# Project2.net
KiCad netlist of a schematic drawn in EAGLE
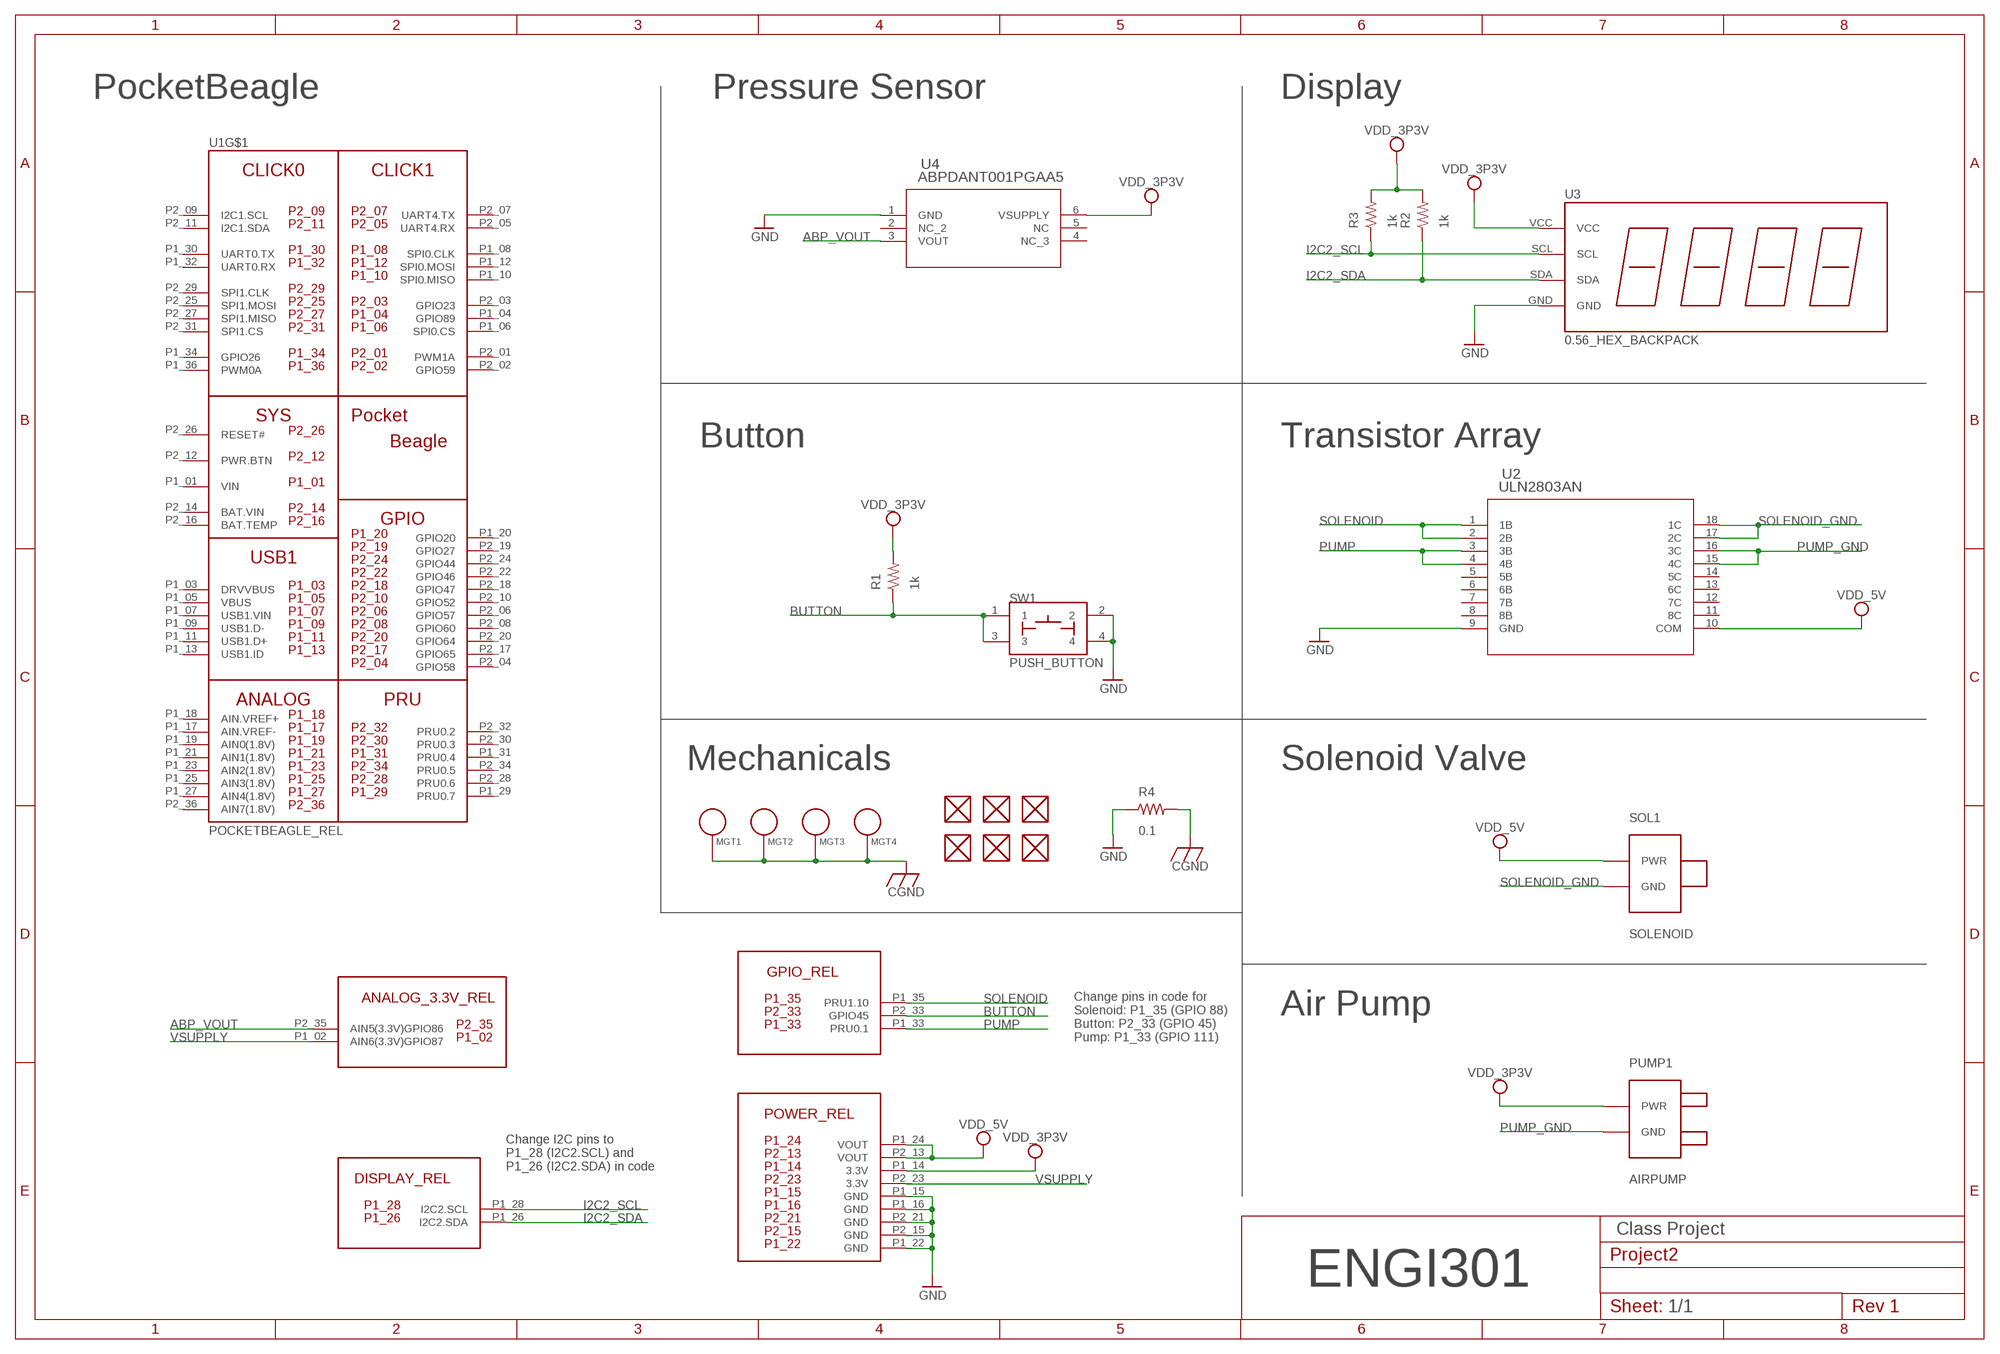
[diagram p0: schematic, sheet 1]

(export (version "E")
  (design (tool "Eeschema 10.0.6"))
  (components
    (comp (ref "FUD1")
      (value "FIDUCIAL")
      (footprint "eagle-import:FIDUCIAL_40MIL")
      (libsource (lib "eagle-import") (part "FIDUCIAL"))
    )
    (comp (ref "FUD2")
      (value "FIDUCIAL")
      (footprint "eagle-import:FIDUCIAL_40MIL")
      (libsource (lib "eagle-import") (part "FIDUCIAL"))
    )
    (comp (ref "FUD3")
      (value "FIDUCIAL")
      (footprint "eagle-import:FIDUCIAL_40MIL")
      (libsource (lib "eagle-import") (part "FIDUCIAL"))
    )
    (comp (ref "FUD4")
      (value "FIDUCIAL")
      (footprint "eagle-import:FIDUCIAL_40MIL")
      (libsource (lib "eagle-import") (part "FIDUCIAL"))
    )
    (comp (ref "FUD5")
      (value "FIDUCIAL")
      (footprint "eagle-import:FIDUCIAL_40MIL")
      (libsource (lib "eagle-import") (part "FIDUCIAL"))
    )
    (comp (ref "FUD6")
      (value "FIDUCIAL")
      (footprint "eagle-import:FIDUCIAL_40MIL")
      (libsource (lib "eagle-import") (part "FIDUCIAL"))
    )
    (comp (ref "MGT1")
      (value "MOUNTING_HOLE")
      (footprint "eagle-import:MOUNTING_HOLE")
      (libsource (lib "eagle-import") (part "MOUNTING_HOLE"))
    )
    (comp (ref "MGT2")
      (value "MOUNTING_HOLE")
      (footprint "eagle-import:MOUNTING_HOLE")
      (libsource (lib "eagle-import") (part "MOUNTING_HOLE"))
    )
    (comp (ref "MGT3")
      (value "MOUNTING_HOLE")
      (footprint "eagle-import:MOUNTING_HOLE")
      (libsource (lib "eagle-import") (part "MOUNTING_HOLE"))
    )
    (comp (ref "MGT4")
      (value "MOUNTING_HOLE")
      (footprint "eagle-import:MOUNTING_HOLE")
      (libsource (lib "eagle-import") (part "MOUNTING_HOLE"))
    )
    (comp (ref "PUMP1")
      (value "AIRPUMP")
      (footprint "eagle-import:AIRPUMP")
      (libsource (lib "eagle-import") (part "AIRPUMP"))
    )
    (comp (ref "R1")
      (value "1k")
      (footprint "eagle-import:R0603")
      (libsource (lib "eagle-import") (part "R_R0603"))
    )
    (comp (ref "R2")
      (value "1k")
      (footprint "eagle-import:R0603")
      (libsource (lib "eagle-import") (part "R_R0603"))
    )
    (comp (ref "R3")
      (value "1k")
      (footprint "eagle-import:R0603")
      (libsource (lib "eagle-import") (part "R_R0603"))
    )
    (comp (ref "R4")
      (value "0.1")
      (footprint "eagle-import:R0603")
      (libsource (lib "eagle-import") (part "R_R0603"))
    )
    (comp (ref "SOL1")
      (value "SOLENOID")
      (footprint "eagle-import:SOLENOID")
      (libsource (lib "eagle-import") (part "SOLENOID"))
    )
    (comp (ref "SW1")
      (value "PUSH_BUTTON")
      (footprint "eagle-import:BUTTON_12.5MM")
      (libsource (lib "eagle-import") (part "PUSH_BUTTON"))
    )
    (comp (ref "U1")
      (value "POCKETBEAGLE_REL")
      (footprint "eagle-import:POCKETBEAGLE")
      (libsource (lib "eagle-import") (part "POCKETBEAGLE_REL"))
    )
    (comp (ref "U2")
      (value "ULN2803AN")
      (footprint "eagle-import:N18_TEX")
      (fields (field (name "COPYRIGHT") "Copyright (C) 2021 Ultra Librarian. All rights reserved."))
      (libsource (lib "eagle-import") (part "ULN2803AN"))
    )
    (comp (ref "U3")
      (value "0.56_HEX_BACKPACK")
      (footprint "eagle-import:0.56_HEX_BACKPACK")
      (libsource (lib "eagle-import") (part "0.56_HEX_BACKPACK"))
    )
    (comp (ref "U4")
      (value "ABPDANT001PGAA5")
      (footprint "eagle-import:ABPDAN_HNW")
      (fields
        (field (name "MANUFACTURER_PART_NUMBER") "ABPDANT005PGAA5")
        (field (name "COPYRIGHT") "Copyright (C) 2021 Ultra Librarian. All rights reserved.")
      )
      (libsource (lib "eagle-import") (part "ABPDANT001PGAA5"))
    )
  )
  (nets
    (net (code "1") (name "/ABP_VOUT") (class "Default")
      (node (ref "U1") (pin "P2_35") (pinfunction "AIN5(3.3V)GPIO86_P2_35") (pintype "bidirectional"))
      (node (ref "U4") (pin "3") (pinfunction "VOUT_3") (pintype "output"))
    )
    (net (code "2") (name "/BAT.VIN") (class "Default")
      (node (ref "U1") (pin "P2_14") (pinfunction "BAT.VIN_P2_14") (pintype "power_in"))
    )
    (net (code "3") (name "/BUTTON") (class "Default")
      (node (ref "R1") (pin "1") (pinfunction "1_1") (pintype "passive"))
      (node (ref "SW1") (pin "1") (pinfunction "1_1") (pintype "bidirectional"))
      (node (ref "SW1") (pin "3") (pinfunction "3_3") (pintype "bidirectional"))
      (node (ref "U1") (pin "P2_33") (pinfunction "GPIO45_P2_33") (pintype "bidirectional"))
    )
    (net (code "4") (name "/I2C2_SCL") (class "Default")
      (node (ref "R3") (pin "1") (pinfunction "1_1") (pintype "passive"))
      (node (ref "U1") (pin "P1_28") (pinfunction "I2C2.SCL_P1_28") (pintype "bidirectional"))
      (node (ref "U3") (pin "SCL") (pinfunction "SCL_SCL") (pintype "bidirectional"))
    )
    (net (code "5") (name "/I2C2_SDA") (class "Default")
      (node (ref "R2") (pin "1") (pinfunction "1_1") (pintype "passive"))
      (node (ref "U1") (pin "P1_26") (pinfunction "I2C2.SDA_P1_26") (pintype "bidirectional"))
      (node (ref "U3") (pin "SDA") (pinfunction "SDA_SDA") (pintype "bidirectional"))
    )
    (net (code "6") (name "/PUMP") (class "Default")
      (node (ref "U1") (pin "P1_33") (pinfunction "PRU0.1_P1_33") (pintype "bidirectional"))
      (node (ref "U2") (pin "3") (pinfunction "3B_3") (pintype "passive"))
      (node (ref "U2") (pin "4") (pinfunction "4B_4") (pintype "passive"))
    )
    (net (code "7") (name "/PUMP_GND") (class "Default")
      (node (ref "PUMP1") (pin "GND1") (pinfunction "GND_GND1") (pintype "bidirectional"))
      (node (ref "U2") (pin "15") (pinfunction "4C_15") (pintype "passive"))
      (node (ref "U2") (pin "16") (pinfunction "3C_16") (pintype "passive"))
    )
    (net (code "8") (name "/SOLENOID") (class "Default")
      (node (ref "U1") (pin "P1_35") (pinfunction "PRU1.10_P1_35") (pintype "bidirectional"))
      (node (ref "U2") (pin "1") (pinfunction "1B_1") (pintype "passive"))
      (node (ref "U2") (pin "2") (pinfunction "2B_2") (pintype "passive"))
    )
    (net (code "9") (name "/SOLENOID_GND") (class "Default")
      (node (ref "SOL1") (pin "GND") (pinfunction "GND_GND") (pintype "bidirectional"))
      (node (ref "U2") (pin "17") (pinfunction "2C_17") (pintype "passive"))
      (node (ref "U2") (pin "18") (pinfunction "1C_18") (pintype "passive"))
    )
    (net (code "10") (name "/VIN") (class "Default")
      (node (ref "U1") (pin "P1_01") (pinfunction "VIN_P1_01") (pintype "power_in"))
    )
    (net (code "11") (name "/VSUPPLY") (class "Default")
      (node (ref "U1") (pin "P1_02") (pinfunction "AIN6(3.3V)GPIO87_P1_02") (pintype "bidirectional"))
      (node (ref "U1") (pin "P2_23") (pinfunction "3.3V_P2_23") (pintype "power_in"))
    )
    (net (code "12") (name "CGND") (class "Default")
      (node (ref "MGT1") (pin "P$1") (pinfunction "P$1_P$1") (pintype "bidirectional"))
      (node (ref "MGT2") (pin "P$1") (pinfunction "P$1_P$1") (pintype "bidirectional"))
      (node (ref "MGT3") (pin "P$1") (pinfunction "P$1_P$1") (pintype "bidirectional"))
      (node (ref "MGT4") (pin "P$1") (pinfunction "P$1_P$1") (pintype "bidirectional"))
      (node (ref "R4") (pin "2") (pinfunction "2_2") (pintype "passive"))
    )
    (net (code "13") (name "GND") (class "Default")
      (node (ref "R4") (pin "1") (pinfunction "1_1") (pintype "passive"))
      (node (ref "SW1") (pin "2") (pinfunction "2_2") (pintype "bidirectional"))
      (node (ref "SW1") (pin "4") (pinfunction "4_4") (pintype "bidirectional"))
      (node (ref "U1") (pin "P1_15") (pinfunction "GND_P1_15") (pintype "power_in"))
      (node (ref "U1") (pin "P1_16") (pinfunction "GND_P1_16") (pintype "power_in"))
      (node (ref "U1") (pin "P1_22") (pinfunction "GND_P1_22") (pintype "power_in"))
      (node (ref "U1") (pin "P2_15") (pinfunction "GND_P2_15") (pintype "power_in"))
      (node (ref "U1") (pin "P2_21") (pinfunction "GND_P2_21") (pintype "power_in"))
      (node (ref "U2") (pin "9") (pinfunction "GND_9") (pintype "passive"))
      (node (ref "U3") (pin "GND") (pinfunction "GND_GND") (pintype "bidirectional"))
      (node (ref "U4") (pin "1") (pinfunction "GND_1") (pintype "passive"))
    )
    (net (code "14") (name "VDD_3P3V") (class "Default")
      (node (ref "PUMP1") (pin "PWR1") (pinfunction "PWR_PWR1") (pintype "bidirectional"))
      (node (ref "R1") (pin "2") (pinfunction "2_2") (pintype "passive"))
      (node (ref "R2") (pin "2") (pinfunction "2_2") (pintype "passive"))
      (node (ref "R3") (pin "2") (pinfunction "2_2") (pintype "passive"))
      (node (ref "U1") (pin "P1_14") (pinfunction "3.3V_P1_14") (pintype "power_in"))
      (node (ref "U3") (pin "VCC") (pinfunction "VCC_VCC") (pintype "power_in"))
      (node (ref "U4") (pin "6") (pinfunction "VSUPPLY_6") (pintype "power_in"))
    )
    (net (code "15") (name "VDD_5V") (class "Default")
      (node (ref "SOL1") (pin "PWR1") (pinfunction "PWR_PWR1") (pintype "bidirectional"))
      (node (ref "U1") (pin "P1_24") (pinfunction "VOUT_P1_24") (pintype "power_in"))
      (node (ref "U1") (pin "P2_13") (pinfunction "VOUT_P2_13") (pintype "power_in"))
      (node (ref "U2") (pin "10") (pinfunction "COM_10") (pintype "passive"))
    )
    (net (code "16") (name "unconnected-(FUD1-PadP$1)") (class "Default")
      (node (ref "FUD1") (pin "P$1") (pinfunction "P$1_P$1") (pintype "no_connect"))
    )
    (net (code "17") (name "unconnected-(FUD2-PadP$1)") (class "Default")
      (node (ref "FUD2") (pin "P$1") (pinfunction "P$1_P$1") (pintype "no_connect"))
    )
    (net (code "18") (name "unconnected-(FUD3-PadP$1)") (class "Default")
      (node (ref "FUD3") (pin "P$1") (pinfunction "P$1_P$1") (pintype "no_connect"))
    )
    (net (code "19") (name "unconnected-(FUD4-PadP$1)") (class "Default")
      (node (ref "FUD4") (pin "P$1") (pinfunction "P$1_P$1") (pintype "no_connect"))
    )
    (net (code "20") (name "unconnected-(FUD5-PadP$1)") (class "Default")
      (node (ref "FUD5") (pin "P$1") (pinfunction "P$1_P$1") (pintype "no_connect"))
    )
    (net (code "21") (name "unconnected-(FUD6-PadP$1)") (class "Default")
      (node (ref "FUD6") (pin "P$1") (pinfunction "P$1_P$1") (pintype "no_connect"))
    )
    (net (code "22") (name "unconnected-(U1A-AIN.VREF+-PadP1_18)") (class "Default")
      (node (ref "U1") (pin "P1_18") (pinfunction "AIN.VREF+_P1_18") (pintype "input"))
    )
    (net (code "23") (name "unconnected-(U1A-AIN.VREF--PadP1_17)") (class "Default")
      (node (ref "U1") (pin "P1_17") (pinfunction "AIN.VREF-_P1_17") (pintype "input"))
    )
    (net (code "24") (name "unconnected-(U1A-AIN0(1.8V)-PadP1_19)") (class "Default")
      (node (ref "U1") (pin "P1_19") (pinfunction "AIN0(1.8V)_P1_19") (pintype "input"))
    )
    (net (code "25") (name "unconnected-(U1A-AIN1(1.8V)-PadP1_21)") (class "Default")
      (node (ref "U1") (pin "P1_21") (pinfunction "AIN1(1.8V)_P1_21") (pintype "input"))
    )
    (net (code "26") (name "unconnected-(U1A-AIN2(1.8V)-PadP1_23)") (class "Default")
      (node (ref "U1") (pin "P1_23") (pinfunction "AIN2(1.8V)_P1_23") (pintype "input"))
    )
    (net (code "27") (name "unconnected-(U1A-AIN3(1.8V)-PadP1_25)") (class "Default")
      (node (ref "U1") (pin "P1_25") (pinfunction "AIN3(1.8V)_P1_25") (pintype "input"))
    )
    (net (code "28") (name "unconnected-(U1A-AIN4(1.8V)-PadP1_27)") (class "Default")
      (node (ref "U1") (pin "P1_27") (pinfunction "AIN4(1.8V)_P1_27") (pintype "input"))
    )
    (net (code "29") (name "unconnected-(U1A-AIN7(1.8V)-PadP2_36)") (class "Default")
      (node (ref "U1") (pin "P2_36") (pinfunction "AIN7(1.8V)_P2_36") (pintype "input"))
    )
    (net (code "30") (name "unconnected-(U1A-BAT.TEMP-PadP2_16)") (class "Default")
      (node (ref "U1") (pin "P2_16") (pinfunction "BAT.TEMP_P2_16") (pintype "input"))
    )
    (net (code "31") (name "unconnected-(U1A-DRVVBUS-PadP1_03)") (class "Default")
      (node (ref "U1") (pin "P1_03") (pinfunction "DRVVBUS_P1_03") (pintype "bidirectional"))
    )
    (net (code "32") (name "unconnected-(U1A-GPIO20-PadP1_20)") (class "Default")
      (node (ref "U1") (pin "P1_20") (pinfunction "GPIO20_P1_20") (pintype "bidirectional"))
    )
    (net (code "33") (name "unconnected-(U1A-GPIO23-PadP2_03)") (class "Default")
      (node (ref "U1") (pin "P2_03") (pinfunction "GPIO23_P2_03") (pintype "bidirectional"))
    )
    (net (code "34") (name "unconnected-(U1A-GPIO26-PadP1_34)") (class "Default")
      (node (ref "U1") (pin "P1_34") (pinfunction "GPIO26_P1_34") (pintype "bidirectional"))
    )
    (net (code "35") (name "unconnected-(U1A-GPIO27-PadP2_19)") (class "Default")
      (node (ref "U1") (pin "P2_19") (pinfunction "GPIO27_P2_19") (pintype "bidirectional"))
    )
    (net (code "36") (name "unconnected-(U1A-GPIO44-PadP2_24)") (class "Default")
      (node (ref "U1") (pin "P2_24") (pinfunction "GPIO44_P2_24") (pintype "bidirectional"))
    )
    (net (code "37") (name "unconnected-(U1A-GPIO46-PadP2_22)") (class "Default")
      (node (ref "U1") (pin "P2_22") (pinfunction "GPIO46_P2_22") (pintype "bidirectional"))
    )
    (net (code "38") (name "unconnected-(U1A-GPIO47-PadP2_18)") (class "Default")
      (node (ref "U1") (pin "P2_18") (pinfunction "GPIO47_P2_18") (pintype "bidirectional"))
    )
    (net (code "39") (name "unconnected-(U1A-GPIO52-PadP2_10)") (class "Default")
      (node (ref "U1") (pin "P2_10") (pinfunction "GPIO52_P2_10") (pintype "bidirectional"))
    )
    (net (code "40") (name "unconnected-(U1A-GPIO57-PadP2_06)") (class "Default")
      (node (ref "U1") (pin "P2_06") (pinfunction "GPIO57_P2_06") (pintype "bidirectional"))
    )
    (net (code "41") (name "unconnected-(U1A-GPIO58-PadP2_04)") (class "Default")
      (node (ref "U1") (pin "P2_04") (pinfunction "GPIO58_P2_04") (pintype "bidirectional"))
    )
    (net (code "42") (name "unconnected-(U1A-GPIO59-PadP2_02)") (class "Default")
      (node (ref "U1") (pin "P2_02") (pinfunction "GPIO59_P2_02") (pintype "bidirectional"))
    )
    (net (code "43") (name "unconnected-(U1A-GPIO60-PadP2_08)") (class "Default")
      (node (ref "U1") (pin "P2_08") (pinfunction "GPIO60_P2_08") (pintype "bidirectional"))
    )
    (net (code "44") (name "unconnected-(U1A-GPIO64-PadP2_20)") (class "Default")
      (node (ref "U1") (pin "P2_20") (pinfunction "GPIO64_P2_20") (pintype "bidirectional"))
    )
    (net (code "45") (name "unconnected-(U1A-GPIO65-PadP2_17)") (class "Default")
      (node (ref "U1") (pin "P2_17") (pinfunction "GPIO65_P2_17") (pintype "bidirectional"))
    )
    (net (code "46") (name "unconnected-(U1A-GPIO89-PadP1_04)") (class "Default")
      (node (ref "U1") (pin "P1_04") (pinfunction "GPIO89_P1_04") (pintype "bidirectional"))
    )
    (net (code "47") (name "unconnected-(U1A-I2C1.SCL-PadP2_09)") (class "Default")
      (node (ref "U1") (pin "P2_09") (pinfunction "I2C1.SCL_P2_09") (pintype "bidirectional"))
    )
    (net (code "48") (name "unconnected-(U1A-I2C1.SDA-PadP2_11)") (class "Default")
      (node (ref "U1") (pin "P2_11") (pinfunction "I2C1.SDA_P2_11") (pintype "bidirectional"))
    )
    (net (code "49") (name "unconnected-(U1A-PRU0.2-PadP2_32)") (class "Default")
      (node (ref "U1") (pin "P2_32") (pinfunction "PRU0.2_P2_32") (pintype "bidirectional"))
    )
    (net (code "50") (name "unconnected-(U1A-PRU0.3-PadP2_30)") (class "Default")
      (node (ref "U1") (pin "P2_30") (pinfunction "PRU0.3_P2_30") (pintype "bidirectional"))
    )
    (net (code "51") (name "unconnected-(U1A-PRU0.4-PadP1_31)") (class "Default")
      (node (ref "U1") (pin "P1_31") (pinfunction "PRU0.4_P1_31") (pintype "bidirectional"))
    )
    (net (code "52") (name "unconnected-(U1A-PRU0.5-PadP2_34)") (class "Default")
      (node (ref "U1") (pin "P2_34") (pinfunction "PRU0.5_P2_34") (pintype "bidirectional"))
    )
    (net (code "53") (name "unconnected-(U1A-PRU0.6-PadP2_28)") (class "Default")
      (node (ref "U1") (pin "P2_28") (pinfunction "PRU0.6_P2_28") (pintype "bidirectional"))
    )
    (net (code "54") (name "unconnected-(U1A-PRU0.7-PadP1_29)") (class "Default")
      (node (ref "U1") (pin "P1_29") (pinfunction "PRU0.7_P1_29") (pintype "bidirectional"))
    )
    (net (code "55") (name "unconnected-(U1A-PWM0A-PadP1_36)") (class "Default")
      (node (ref "U1") (pin "P1_36") (pinfunction "PWM0A_P1_36") (pintype "bidirectional"))
    )
    (net (code "56") (name "unconnected-(U1A-PWM1A-PadP2_01)") (class "Default")
      (node (ref "U1") (pin "P2_01") (pinfunction "PWM1A_P2_01") (pintype "bidirectional"))
    )
    (net (code "57") (name "unconnected-(U1A-PWR.BTN-PadP2_12)") (class "Default")
      (node (ref "U1") (pin "P2_12") (pinfunction "PWR.BTN_P2_12") (pintype "input"))
    )
    (net (code "58") (name "unconnected-(U1A-RESET#-PadP2_26)") (class "Default")
      (node (ref "U1") (pin "P2_26") (pinfunction "RESET#_P2_26") (pintype "input"))
    )
    (net (code "59") (name "unconnected-(U1A-SPI0.CLK-PadP1_08)") (class "Default")
      (node (ref "U1") (pin "P1_08") (pinfunction "SPI0.CLK_P1_08") (pintype "bidirectional"))
    )
    (net (code "60") (name "unconnected-(U1A-SPI0.CS-PadP1_06)") (class "Default")
      (node (ref "U1") (pin "P1_06") (pinfunction "SPI0.CS_P1_06") (pintype "bidirectional"))
    )
    (net (code "61") (name "unconnected-(U1A-SPI0.MISO-PadP1_10)") (class "Default")
      (node (ref "U1") (pin "P1_10") (pinfunction "SPI0.MISO_P1_10") (pintype "bidirectional"))
    )
    (net (code "62") (name "unconnected-(U1A-SPI0.MOSI-PadP1_12)") (class "Default")
      (node (ref "U1") (pin "P1_12") (pinfunction "SPI0.MOSI_P1_12") (pintype "bidirectional"))
    )
    (net (code "63") (name "unconnected-(U1A-SPI1.CLK-PadP2_29)") (class "Default")
      (node (ref "U1") (pin "P2_29") (pinfunction "SPI1.CLK_P2_29") (pintype "bidirectional"))
    )
    (net (code "64") (name "unconnected-(U1A-SPI1.CS-PadP2_31)") (class "Default")
      (node (ref "U1") (pin "P2_31") (pinfunction "SPI1.CS_P2_31") (pintype "bidirectional"))
    )
    (net (code "65") (name "unconnected-(U1A-SPI1.MISO-PadP2_27)") (class "Default")
      (node (ref "U1") (pin "P2_27") (pinfunction "SPI1.MISO_P2_27") (pintype "bidirectional"))
    )
    (net (code "66") (name "unconnected-(U1A-SPI1.MOSI-PadP2_25)") (class "Default")
      (node (ref "U1") (pin "P2_25") (pinfunction "SPI1.MOSI_P2_25") (pintype "bidirectional"))
    )
    (net (code "67") (name "unconnected-(U1A-UART0.RX-PadP1_32)") (class "Default")
      (node (ref "U1") (pin "P1_32") (pinfunction "UART0.RX_P1_32") (pintype "bidirectional"))
    )
    (net (code "68") (name "unconnected-(U1A-UART0.TX-PadP1_30)") (class "Default")
      (node (ref "U1") (pin "P1_30") (pinfunction "UART0.TX_P1_30") (pintype "bidirectional"))
    )
    (net (code "69") (name "unconnected-(U1A-UART4.RX-PadP2_05)") (class "Default")
      (node (ref "U1") (pin "P2_05") (pinfunction "UART4.RX_P2_05") (pintype "bidirectional"))
    )
    (net (code "70") (name "unconnected-(U1A-UART4.TX-PadP2_07)") (class "Default")
      (node (ref "U1") (pin "P2_07") (pinfunction "UART4.TX_P2_07") (pintype "bidirectional"))
    )
    (net (code "71") (name "unconnected-(U1A-USB1.D+-PadP1_11)") (class "Default")
      (node (ref "U1") (pin "P1_11") (pinfunction "USB1.D+_P1_11") (pintype "bidirectional"))
    )
    (net (code "72") (name "unconnected-(U1A-USB1.D--PadP1_09)") (class "Default")
      (node (ref "U1") (pin "P1_09") (pinfunction "USB1.D-_P1_09") (pintype "bidirectional"))
    )
    (net (code "73") (name "unconnected-(U1A-USB1.ID-PadP1_13)") (class "Default")
      (node (ref "U1") (pin "P1_13") (pinfunction "USB1.ID_P1_13") (pintype "bidirectional"))
    )
    (net (code "74") (name "unconnected-(U1A-USB1.VIN-PadP1_07)") (class "Default")
      (node (ref "U1") (pin "P1_07") (pinfunction "USB1.VIN_P1_07") (pintype "bidirectional"))
    )
    (net (code "75") (name "unconnected-(U1A-VBUS-PadP1_05)") (class "Default")
      (node (ref "U1") (pin "P1_05") (pinfunction "VBUS_P1_05") (pintype "bidirectional"))
    )
    (net (code "76") (name "unconnected-(U2-5B-Pad5)") (class "Default")
      (node (ref "U2") (pin "5") (pinfunction "5B_5") (pintype "passive"))
    )
    (net (code "77") (name "unconnected-(U2-5C-Pad14)") (class "Default")
      (node (ref "U2") (pin "14") (pinfunction "5C_14") (pintype "passive"))
    )
    (net (code "78") (name "unconnected-(U2-6B-Pad6)") (class "Default")
      (node (ref "U2") (pin "6") (pinfunction "6B_6") (pintype "passive"))
    )
    (net (code "79") (name "unconnected-(U2-6C-Pad13)") (class "Default")
      (node (ref "U2") (pin "13") (pinfunction "6C_13") (pintype "passive"))
    )
    (net (code "80") (name "unconnected-(U2-7B-Pad7)") (class "Default")
      (node (ref "U2") (pin "7") (pinfunction "7B_7") (pintype "passive"))
    )
    (net (code "81") (name "unconnected-(U2-7C-Pad12)") (class "Default")
      (node (ref "U2") (pin "12") (pinfunction "7C_12") (pintype "passive"))
    )
    (net (code "82") (name "unconnected-(U2-8B-Pad8)") (class "Default")
      (node (ref "U2") (pin "8") (pinfunction "8B_8") (pintype "passive"))
    )
    (net (code "83") (name "unconnected-(U2-8C-Pad11)") (class "Default")
      (node (ref "U2") (pin "11") (pinfunction "8C_11") (pintype "passive"))
    )
    (net (code "84") (name "unconnected-(U4-NC-Pad5)") (class "Default")
      (node (ref "U4") (pin "5") (pinfunction "NC_5") (pintype "no_connect"))
    )
    (net (code "85") (name "unconnected-(U4-NC_2-Pad2)") (class "Default")
      (node (ref "U4") (pin "2") (pinfunction "NC_2_2") (pintype "no_connect"))
    )
    (net (code "86") (name "unconnected-(U4-NC_3-Pad4)") (class "Default")
      (node (ref "U4") (pin "4") (pinfunction "NC_3_4") (pintype "no_connect"))
    )
  )
)
